# JTAG_Interface.net
KiCad netlist of a schematic drawn in Altium Designer
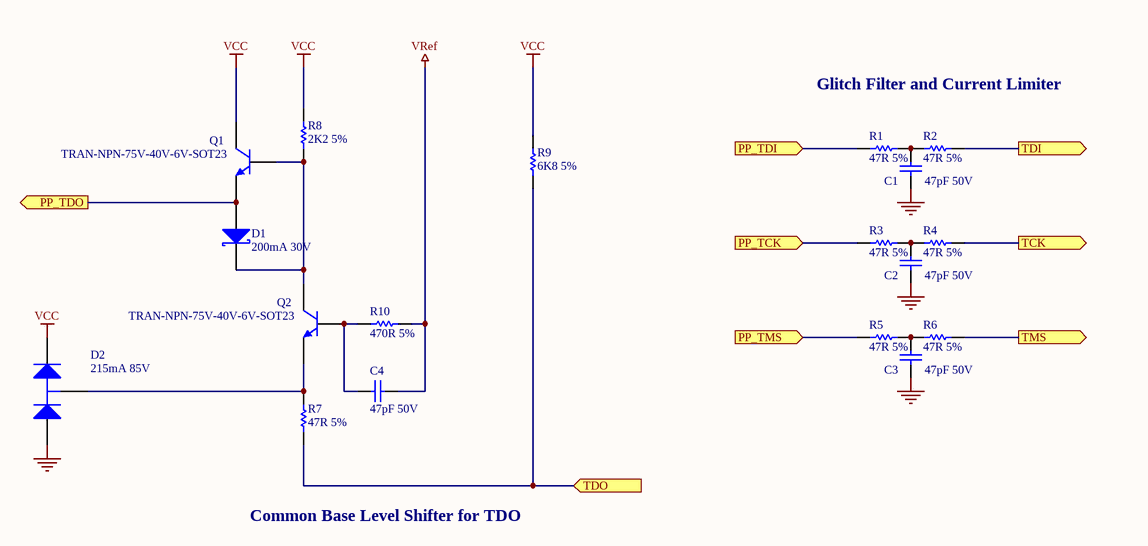
[diagram p0: JTAG Interface.SchDoc]

(export (version "E")
  (design (tool "Eeschema 10.0.6"))
  (components
    (comp (ref "C1")
      (value "47pF 50V")
      (footprint "CAPC2012")
      (description "Capacitor")
      (libsource (lib "Altium Design Library") (part "CAP-NP"))
    )
    (comp (ref "C2")
      (value "47pF 50V")
      (footprint "CAPC2012")
      (description "Capacitor")
      (libsource (lib "Altium Design Library") (part "CAP-NP"))
    )
    (comp (ref "C3")
      (value "47pF 50V")
      (footprint "CAPC2012")
      (description "Capacitor")
      (libsource (lib "Altium Design Library") (part "CAP-NP"))
    )
    (comp (ref "C4")
      (value "47pF 50V")
      (footprint "CAPC2012")
      (description "Capacitor")
      (libsource (lib "Altium Design Library") (part "CAP-NP"))
    )
    (comp (ref "D1")
      (value "200mA 30V")
      (footprint "SOT95P230-3")
      (description "Schottky Barrier Single Diode")
      (libsource (lib "Altium Design Library") (part "DIO-SCHOTTKY-1S-SOT23"))
    )
    (comp (ref "D2")
      (value "215mA 85V")
      (footprint "SOT95P230-3")
      (description "Silicon Switching Diode Array for High-Speed Switching")
      (libsource (lib "Altium Design Library") (part "DIO-2S"))
    )
    (comp (ref "Q1")
      (value "TRAN-NPN-75V-40V-6V-SOT23")
      (footprint "SOT95P230-3")
      (description "General Purpose Transistor NPN Silicon")
      (libsource (lib "Altium Design Library") (part "TRA-NPN"))
    )
    (comp (ref "Q2")
      (value "TRAN-NPN-75V-40V-6V-SOT23")
      (footprint "SOT95P230-3")
      (description "General Purpose Transistor NPN Silicon")
      (libsource (lib "Altium Design Library") (part "TRA-NPN"))
    )
    (comp (ref "R1")
      (value "47R 5%")
      (footprint "RESC2012")
      (description "Resistor")
      (libsource (lib "Altium Design Library") (part "RES"))
    )
    (comp (ref "R2")
      (value "47R 5%")
      (footprint "RESC2012")
      (description "Resistor")
      (libsource (lib "Altium Design Library") (part "RES"))
    )
    (comp (ref "R3")
      (value "47R 5%")
      (footprint "RESC2012")
      (description "Resistor")
      (libsource (lib "Altium Design Library") (part "RES"))
    )
    (comp (ref "R4")
      (value "47R 5%")
      (footprint "RESC2012")
      (description "Resistor")
      (libsource (lib "Altium Design Library") (part "RES"))
    )
    (comp (ref "R5")
      (value "47R 5%")
      (footprint "RESC2012")
      (description "Resistor")
      (libsource (lib "Altium Design Library") (part "RES"))
    )
    (comp (ref "R6")
      (value "47R 5%")
      (footprint "RESC2012")
      (description "Resistor")
      (libsource (lib "Altium Design Library") (part "RES"))
    )
    (comp (ref "R7")
      (value "47R 5%")
      (footprint "RESC2012")
      (description "Resistor")
      (libsource (lib "Altium Design Library") (part "RES"))
    )
    (comp (ref "R8")
      (value "2K2 5%")
      (footprint "RESC2012")
      (description "Resistor")
      (libsource (lib "Altium Design Library") (part "RES"))
    )
    (comp (ref "R9")
      (value "6K8 5%")
      (footprint "RESC2012")
      (description "Resistor")
      (libsource (lib "Altium Design Library") (part "RES"))
    )
    (comp (ref "R10")
      (value "470R 5%")
      (footprint "RESC2012")
      (description "Resistor")
      (libsource (lib "Altium Design Library") (part "RES"))
    )
  )
  (nets
    (net (code "1") (name "/PP_TCK") (class "Default")
      (node (ref "R3") (pin "1") (pinfunction "1_1") (pintype "passive"))
    )
    (net (code "2") (name "/PP_TDI") (class "Default")
      (node (ref "R1") (pin "1") (pinfunction "1_1") (pintype "passive"))
    )
    (net (code "3") (name "/PP_TDO") (class "Default")
      (node (ref "D1") (pin "1") (pinfunction "A_1") (pintype "passive"))
      (node (ref "Q1") (pin "2") (pinfunction "E_2") (pintype "passive"))
    )
    (net (code "4") (name "/PP_TMS") (class "Default")
      (node (ref "R5") (pin "1") (pinfunction "1_1") (pintype "passive"))
    )
    (net (code "5") (name "/TCK") (class "Default")
      (node (ref "R4") (pin "2") (pinfunction "2_2") (pintype "passive"))
    )
    (net (code "6") (name "/TDI") (class "Default")
      (node (ref "R2") (pin "2") (pinfunction "2_2") (pintype "passive"))
    )
    (net (code "7") (name "/TDO") (class "Default")
      (node (ref "R7") (pin "1") (pinfunction "1_1") (pintype "passive"))
      (node (ref "R9") (pin "1") (pinfunction "1_1") (pintype "passive"))
    )
    (net (code "8") (name "/TMS") (class "Default")
      (node (ref "R6") (pin "2") (pinfunction "2_2") (pintype "passive"))
    )
    (net (code "9") (name "GND") (class "Default")
      (node (ref "C1") (pin "2") (pinfunction "2_2") (pintype "passive"))
      (node (ref "C2") (pin "2") (pinfunction "2_2") (pintype "passive"))
      (node (ref "C3") (pin "2") (pinfunction "2_2") (pintype "passive"))
      (node (ref "D2") (pin "1") (pinfunction "A_1") (pintype "passive"))
    )
    (net (code "10") (name "Net-(C1-Pad1)") (class "Default")
      (node (ref "C1") (pin "1") (pinfunction "1_1") (pintype "passive"))
      (node (ref "R1") (pin "2") (pinfunction "2_2") (pintype "passive"))
      (node (ref "R2") (pin "1") (pinfunction "1_1") (pintype "passive"))
    )
    (net (code "11") (name "Net-(C2-Pad1)") (class "Default")
      (node (ref "C2") (pin "1") (pinfunction "1_1") (pintype "passive"))
      (node (ref "R3") (pin "2") (pinfunction "2_2") (pintype "passive"))
      (node (ref "R4") (pin "1") (pinfunction "1_1") (pintype "passive"))
    )
    (net (code "12") (name "Net-(C3-Pad1)") (class "Default")
      (node (ref "C3") (pin "1") (pinfunction "1_1") (pintype "passive"))
      (node (ref "R5") (pin "2") (pinfunction "2_2") (pintype "passive"))
      (node (ref "R6") (pin "1") (pinfunction "1_1") (pintype "passive"))
    )
    (net (code "13") (name "Net-(D1-k)") (class "Default")
      (node (ref "D1") (pin "3") (pinfunction "k_3") (pintype "passive"))
      (node (ref "Q1") (pin "1") (pinfunction "B_1") (pintype "passive"))
      (node (ref "Q2") (pin "3") (pinfunction "C_3") (pintype "passive"))
      (node (ref "R8") (pin "1") (pinfunction "1_1") (pintype "passive"))
    )
    (net (code "14") (name "Net-(D2-C)") (class "Default")
      (node (ref "D2") (pin "3") (pinfunction "C_3") (pintype "passive"))
      (node (ref "Q2") (pin "2") (pinfunction "E_2") (pintype "passive"))
      (node (ref "R7") (pin "2") (pinfunction "2_2") (pintype "passive"))
    )
    (net (code "15") (name "Net-(Q2-B)") (class "Default")
      (node (ref "C4") (pin "1") (pinfunction "1_1") (pintype "passive"))
      (node (ref "Q2") (pin "1") (pinfunction "B_1") (pintype "passive"))
      (node (ref "R10") (pin "2") (pinfunction "2_2") (pintype "passive"))
    )
    (net (code "16") (name "VCC") (class "Default")
      (node (ref "D2") (pin "2") (pinfunction "K_2") (pintype "passive"))
      (node (ref "Q1") (pin "3") (pinfunction "C_3") (pintype "passive"))
      (node (ref "R8") (pin "2") (pinfunction "2_2") (pintype "passive"))
      (node (ref "R9") (pin "2") (pinfunction "2_2") (pintype "passive"))
    )
    (net (code "17") (name "VRef") (class "Default")
      (node (ref "C4") (pin "2") (pinfunction "2_2") (pintype "passive"))
      (node (ref "R10") (pin "1") (pinfunction "1_1") (pintype "passive"))
    )
    (net (code "18") (name "unconnected-(D1-Pad2)") (class "Default")
      (node (ref "D1") (pin "2") (pintype "passive"))
    )
  )
)
